# Multiplexers.net
KiCad netlist of a schematic drawn in Altium Designer
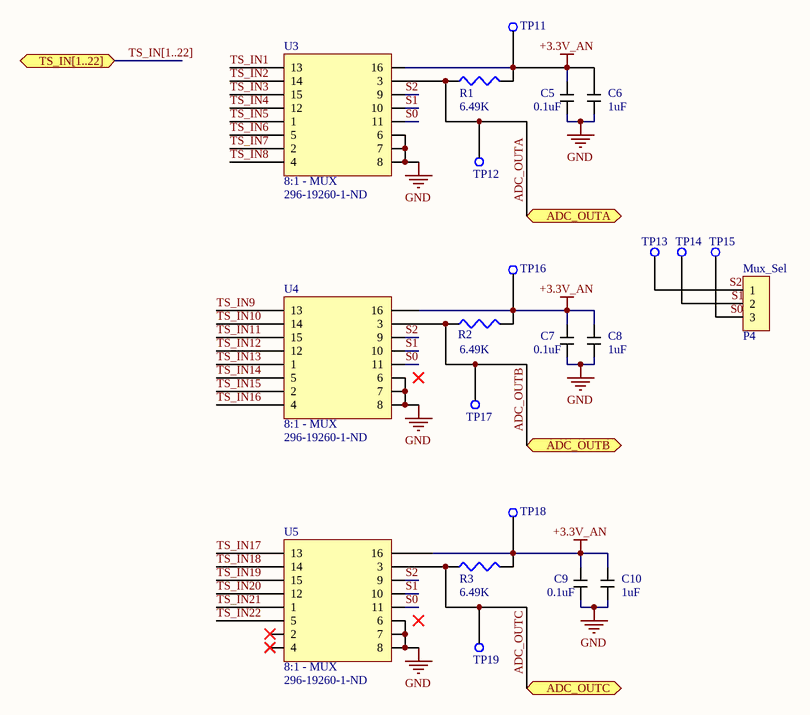
[diagram p0: Multiplexers.SchDoc]

(export (version "E")
  (design (tool "Eeschema 10.0.6"))
  (components
    (comp (ref "C5")
      (value "0.1uF")
      (footprint "PCB_Librayr:0.1uF_Kemet")
      (description "C0603C101K8GAC7867 Kemet Capacitor")
      (libsource (lib "Schematic_Library") (part "0.1uF Cap"))
    )
    (comp (ref "C6")
      (value "1uF")
      (footprint "PCB_Librayr:1uf_Samsung")
      (description "1uF Samsung Cap")
      (libsource (lib "Schematic_Library") (part "1uF Samsung Cap"))
    )
    (comp (ref "C7")
      (value "0.1uF")
      (footprint "PCB_Librayr:0.1uF_Kemet")
      (description "C0603C101K8GAC7867 Kemet Capacitor")
      (libsource (lib "Schematic_Library") (part "0.1uF Cap"))
    )
    (comp (ref "C8")
      (value "1uF")
      (footprint "PCB_Librayr:1uf_Samsung")
      (description "1uF Samsung Cap")
      (libsource (lib "Schematic_Library") (part "1uF Samsung Cap"))
    )
    (comp (ref "C9")
      (value "0.1uF")
      (footprint "PCB_Librayr:0.1uF_Kemet")
      (description "C0603C101K8GAC7867 Kemet Capacitor")
      (libsource (lib "Schematic_Library") (part "0.1uF Cap"))
    )
    (comp (ref "C10")
      (value "1uF")
      (footprint "PCB_Librayr:1uf_Samsung")
      (description "1uF Samsung Cap")
      (libsource (lib "Schematic_Library") (part "1uF Samsung Cap"))
    )
    (comp (ref "P4")
      (value "Mux_Sel")
      (footprint "3-Screw-terminal-Mux-Select")
      (description "Mux Select")
      (fields
        (field (name "MANUFACTURER") "Wurth Electronics")
        (field (name "MANUFACTURER PART NUMBER") "691103110003")
      )
      (libsource (lib "Schematic_Library") (part "3-Screw-Terminal-Mux-Select"))
    )
    (comp (ref "R1")
      (value "6.49kOhm SMD Resistor")
      (footprint "RESC2012X06N")
      (fields
        (field (name "MANUFACTURER") "Panasonic")
        (field (name "MANUFACTURER PART NUMBER") "ERA6AEB6491V")
        (field (name "TOLERANCE") "0.1%")
        (field (name "RESISTANCE") "6.49K")
      )
      (libsource (lib "Schematic_Library") (part "6.49kOhm SMD Resistor"))
    )
    (comp (ref "R2")
      (value "6.49kOhm SMD Resistor")
      (footprint "RESC2012X06N")
      (fields
        (field (name "MANUFACTURER") "Panasonic")
        (field (name "MANUFACTURER PART NUMBER") "ERA6AEB6491V")
        (field (name "TOLERANCE") "0.1%")
        (field (name "RESISTANCE") "6.49K")
      )
      (libsource (lib "Schematic_Library") (part "6.49kOhm SMD Resistor"))
    )
    (comp (ref "R3")
      (value "6.49kOhm SMD Resistor")
      (footprint "RESC2012X06N")
      (fields
        (field (name "MANUFACTURER") "Panasonic")
        (field (name "MANUFACTURER PART NUMBER") "ERA6AEB6491V")
        (field (name "TOLERANCE") "0.1%")
        (field (name "RESISTANCE") "6.49K")
      )
      (libsource (lib "Schematic_Library") (part "6.49kOhm SMD Resistor"))
    )
    (comp (ref "TP11")
      (value "Test Point")
      (footprint "Test Point")
      (libsource (lib "Schematic_Library") (part "Test Point"))
    )
    (comp (ref "TP12")
      (value "Test Point")
      (footprint "Test Point")
      (libsource (lib "Schematic_Library") (part "Test Point"))
    )
    (comp (ref "TP13")
      (value "Test Point")
      (footprint "Test Point")
      (libsource (lib "Schematic_Library") (part "Test Point"))
    )
    (comp (ref "TP14")
      (value "Test Point")
      (footprint "Test Point")
      (libsource (lib "Schematic_Library") (part "Test Point"))
    )
    (comp (ref "TP15")
      (value "Test Point")
      (footprint "Test Point")
      (libsource (lib "Schematic_Library") (part "Test Point"))
    )
    (comp (ref "TP16")
      (value "Test Point")
      (footprint "Test Point")
      (libsource (lib "Schematic_Library") (part "Test Point"))
    )
    (comp (ref "TP17")
      (value "Test Point")
      (footprint "Test Point")
      (libsource (lib "Schematic_Library") (part "Test Point"))
    )
    (comp (ref "TP18")
      (value "Test Point")
      (footprint "Test Point")
      (libsource (lib "Schematic_Library") (part "Test Point"))
    )
    (comp (ref "TP19")
      (value "Test Point")
      (footprint "Test Point")
      (libsource (lib "Schematic_Library") (part "Test Point"))
    )
    (comp (ref "U3")
      (value "8:1 - MUX")
      (footprint "SOP127P600X175")
      (fields
        (field (name "MANUFACTURER") "Texas Instruments")
        (field (name "MANUFACTURER PART NUMBER") "SN74LV4051ATPWRQ1")
        (field (name "SUPPLIER PART NUMBER 1") "296-19260-1-ND")
      )
      (libsource (lib "Schematic_Library") (part "8{colon}1 - MUX"))
    )
    (comp (ref "U4")
      (value "8:1 - MUX")
      (footprint "SOP127P600X175")
      (fields
        (field (name "MANUFACTURER") "Texas Instruments")
        (field (name "MANUFACTURER PART NUMBER") "SN74LV4051ATPWRQ1")
        (field (name "SUPPLIER PART NUMBER 1") "296-19260-1-ND")
      )
      (libsource (lib "Schematic_Library") (part "8{colon}1 - MUX"))
    )
    (comp (ref "U5")
      (value "8:1 - MUX")
      (footprint "SOP127P600X175")
      (fields
        (field (name "MANUFACTURER") "Texas Instruments")
        (field (name "MANUFACTURER PART NUMBER") "SN74LV4051ATPWRQ1")
        (field (name "SUPPLIER PART NUMBER 1") "296-19260-1-ND")
      )
      (libsource (lib "Schematic_Library") (part "8{colon}1 - MUX"))
    )
  )
  (nets
    (net (code "1") (name "+3.3V_AN") (class "Default")
      (node (ref "C10") (pin "2") (pinfunction "2_2") (pintype "passive"))
      (node (ref "C5") (pin "2") (pinfunction "2_2") (pintype "passive"))
      (node (ref "C6") (pin "2") (pinfunction "2_2") (pintype "passive"))
      (node (ref "C7") (pin "2") (pinfunction "2_2") (pintype "passive"))
      (node (ref "C8") (pin "2") (pinfunction "2_2") (pintype "passive"))
      (node (ref "C9") (pin "2") (pinfunction "2_2") (pintype "passive"))
      (node (ref "R1") (pin "2") (pinfunction "2_2") (pintype "passive"))
      (node (ref "R2") (pin "2") (pinfunction "2_2") (pintype "passive"))
      (node (ref "R3") (pin "2") (pinfunction "2_2") (pintype "passive"))
      (node (ref "TP11") (pin "1") (pinfunction "1_1") (pintype "passive"))
      (node (ref "TP16") (pin "1") (pinfunction "1_1") (pintype "passive"))
      (node (ref "TP18") (pin "1") (pinfunction "1_1") (pintype "passive"))
      (node (ref "U3") (pin "16") (pinfunction "16_16") (pintype "passive"))
      (node (ref "U4") (pin "16") (pinfunction "16_16") (pintype "passive"))
      (node (ref "U5") (pin "16") (pinfunction "16_16") (pintype "passive"))
    )
    (net (code "2") (name "/ADC_OUTA") (class "Default")
      (node (ref "R1") (pin "1") (pinfunction "1_1") (pintype "passive"))
      (node (ref "TP12") (pin "1") (pinfunction "1_1") (pintype "passive"))
      (node (ref "U3") (pin "3") (pinfunction "3_3") (pintype "passive"))
    )
    (net (code "3") (name "/ADC_OUTB") (class "Default")
      (node (ref "R2") (pin "1") (pinfunction "1_1") (pintype "passive"))
      (node (ref "TP17") (pin "1") (pinfunction "1_1") (pintype "passive"))
      (node (ref "U4") (pin "3") (pinfunction "3_3") (pintype "passive"))
    )
    (net (code "4") (name "/ADC_OUTC") (class "Default")
      (node (ref "R3") (pin "1") (pinfunction "1_1") (pintype "passive"))
      (node (ref "TP19") (pin "1") (pinfunction "1_1") (pintype "passive"))
      (node (ref "U5") (pin "3") (pinfunction "3_3") (pintype "passive"))
    )
    (net (code "5") (name "/S0") (class "Default")
      (node (ref "U3") (pin "11") (pinfunction "11_11") (pintype "passive"))
      (node (ref "U4") (pin "11") (pinfunction "11_11") (pintype "passive"))
      (node (ref "U5") (pin "11") (pinfunction "11_11") (pintype "passive"))
    )
    (net (code "6") (name "/S1") (class "Default")
      (node (ref "U3") (pin "10") (pinfunction "10_10") (pintype "passive"))
      (node (ref "U4") (pin "10") (pinfunction "10_10") (pintype "passive"))
      (node (ref "U5") (pin "10") (pinfunction "10_10") (pintype "passive"))
    )
    (net (code "7") (name "/S2") (class "Default")
      (node (ref "P4") (pin "1") (pinfunction "1_1") (pintype "passive"))
      (node (ref "TP13") (pin "1") (pinfunction "1_1") (pintype "passive"))
      (node (ref "U3") (pin "9") (pinfunction "9_9") (pintype "passive"))
      (node (ref "U4") (pin "9") (pinfunction "9_9") (pintype "passive"))
      (node (ref "U5") (pin "9") (pinfunction "9_9") (pintype "passive"))
    )
    (net (code "8") (name "/TS_IN1") (class "Default")
      (node (ref "U3") (pin "13") (pinfunction "13_13") (pintype "passive"))
    )
    (net (code "9") (name "/TS_IN2") (class "Default")
      (node (ref "U3") (pin "14") (pinfunction "14_14") (pintype "passive"))
    )
    (net (code "10") (name "/TS_IN3") (class "Default")
      (node (ref "U3") (pin "15") (pinfunction "15_15") (pintype "passive"))
    )
    (net (code "11") (name "/TS_IN4") (class "Default")
      (node (ref "U3") (pin "12") (pinfunction "12_12") (pintype "passive"))
    )
    (net (code "12") (name "/TS_IN5") (class "Default")
      (node (ref "U3") (pin "1") (pinfunction "1_1") (pintype "passive"))
    )
    (net (code "13") (name "/TS_IN6") (class "Default")
      (node (ref "U3") (pin "5") (pinfunction "5_5") (pintype "passive"))
    )
    (net (code "14") (name "/TS_IN7") (class "Default")
      (node (ref "U3") (pin "2") (pinfunction "2_2") (pintype "passive"))
    )
    (net (code "15") (name "/TS_IN8") (class "Default")
      (node (ref "U3") (pin "4") (pinfunction "4_4") (pintype "passive"))
    )
    (net (code "16") (name "/TS_IN9") (class "Default")
      (node (ref "U4") (pin "13") (pinfunction "13_13") (pintype "passive"))
    )
    (net (code "17") (name "/TS_IN10") (class "Default")
      (node (ref "U4") (pin "14") (pinfunction "14_14") (pintype "passive"))
    )
    (net (code "18") (name "/TS_IN11") (class "Default")
      (node (ref "U4") (pin "15") (pinfunction "15_15") (pintype "passive"))
    )
    (net (code "19") (name "/TS_IN12") (class "Default")
      (node (ref "U4") (pin "12") (pinfunction "12_12") (pintype "passive"))
    )
    (net (code "20") (name "/TS_IN13") (class "Default")
      (node (ref "U4") (pin "1") (pinfunction "1_1") (pintype "passive"))
    )
    (net (code "21") (name "/TS_IN14") (class "Default")
      (node (ref "U4") (pin "5") (pinfunction "5_5") (pintype "passive"))
    )
    (net (code "22") (name "/TS_IN15") (class "Default")
      (node (ref "U4") (pin "2") (pinfunction "2_2") (pintype "passive"))
    )
    (net (code "23") (name "/TS_IN16") (class "Default")
      (node (ref "U4") (pin "4") (pinfunction "4_4") (pintype "passive"))
    )
    (net (code "24") (name "/TS_IN17") (class "Default")
      (node (ref "U5") (pin "13") (pinfunction "13_13") (pintype "passive"))
    )
    (net (code "25") (name "/TS_IN18") (class "Default")
      (node (ref "U5") (pin "14") (pinfunction "14_14") (pintype "passive"))
    )
    (net (code "26") (name "/TS_IN19") (class "Default")
      (node (ref "U5") (pin "15") (pinfunction "15_15") (pintype "passive"))
    )
    (net (code "27") (name "/TS_IN20") (class "Default")
      (node (ref "U5") (pin "12") (pinfunction "12_12") (pintype "passive"))
    )
    (net (code "28") (name "/TS_IN21") (class "Default")
      (node (ref "U5") (pin "1") (pinfunction "1_1") (pintype "passive"))
    )
    (net (code "29") (name "/TS_IN22") (class "Default")
      (node (ref "U5") (pin "5") (pinfunction "5_5") (pintype "passive"))
    )
    (net (code "31") (name "GND") (class "Default")
      (node (ref "C10") (pin "1") (pinfunction "1_1") (pintype "passive"))
      (node (ref "C5") (pin "1") (pinfunction "1_1") (pintype "passive"))
      (node (ref "C6") (pin "1") (pinfunction "1_1") (pintype "passive"))
      (node (ref "C7") (pin "1") (pinfunction "1_1") (pintype "passive"))
      (node (ref "C8") (pin "1") (pinfunction "1_1") (pintype "passive"))
      (node (ref "C9") (pin "1") (pinfunction "1_1") (pintype "passive"))
      (node (ref "U3") (pin "6") (pinfunction "6_6") (pintype "passive"))
      (node (ref "U3") (pin "7") (pinfunction "7_7") (pintype "passive"))
      (node (ref "U3") (pin "8") (pinfunction "8_8") (pintype "passive"))
      (node (ref "U4") (pin "6") (pinfunction "6_6") (pintype "passive"))
      (node (ref "U4") (pin "7") (pinfunction "7_7") (pintype "passive"))
      (node (ref "U4") (pin "8") (pinfunction "8_8") (pintype "passive"))
      (node (ref "U5") (pin "6") (pinfunction "6_6") (pintype "passive"))
      (node (ref "U5") (pin "7") (pinfunction "7_7") (pintype "passive"))
      (node (ref "U5") (pin "8") (pinfunction "8_8") (pintype "passive"))
    )
    (net (code "32") (name "Net-(P4-Pad2)") (class "Default")
      (node (ref "P4") (pin "2") (pinfunction "2_2") (pintype "passive"))
      (node (ref "TP14") (pin "1") (pinfunction "1_1") (pintype "passive"))
    )
    (net (code "33") (name "Net-(P4-Pad3)") (class "Default")
      (node (ref "P4") (pin "3") (pinfunction "3_3") (pintype "passive"))
      (node (ref "TP15") (pin "1") (pinfunction "1_1") (pintype "passive"))
    )
    (net (code "34") (name "unconnected-(U5-Pad2)") (class "Default")
      (node (ref "U5") (pin "2") (pinfunction "2_2") (pintype "passive+no_connect"))
    )
    (net (code "35") (name "unconnected-(U5-Pad4)") (class "Default")
      (node (ref "U5") (pin "4") (pinfunction "4_4") (pintype "passive+no_connect"))
    )
  )
)
